# DRLPWM.net
KiCad netlist of a schematic drawn in Altium Designer
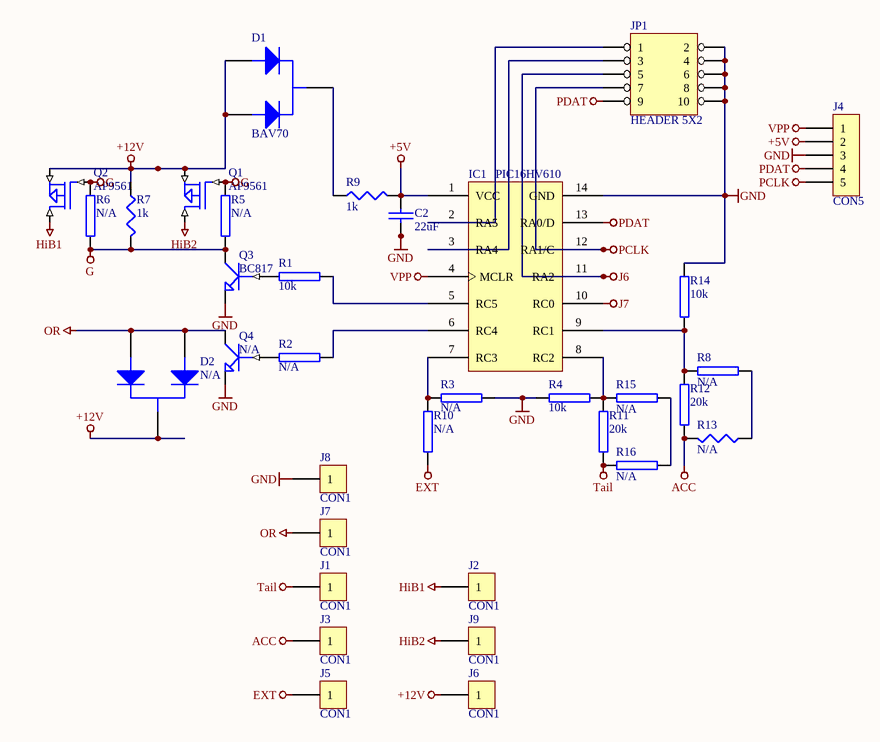
[diagram p0: DRLPWM.SchDoc]

(export (version "E")
  (design (tool "Eeschema 10.0.6"))
  (components
    (comp (ref "C2") (value "22uF") (footprint "0805") (libsource (lib "*") (part "CAP")))
    (comp (ref "D1")
      (value "BAV70")
      (footprint "SOT-23")
      (libsource (lib "Devices") (part "DUAL DIODE BAV70"))
    )
    (comp (ref "D2") (value "N/A") (footprint "SOT-23") (libsource (lib "Devices") (part "DUAL DIODE BAV70")))
    (comp (ref "IC1") (value "PIC16HV610") (footprint "SO-14") (libsource (lib "*") (part "PIC16HV610")))
    (comp (ref "J1")
      (value "CON1")
      (footprint "SIP1 - WIRE")
      (description "Connector")
      (libsource (lib "Miscellaneous Devices") (part "CON1"))
    )
    (comp (ref "J2")
      (value "CON1")
      (footprint "SIP1 - WIRE")
      (description "Connector")
      (libsource (lib "Miscellaneous Devices") (part "CON1"))
    )
    (comp (ref "J3")
      (value "CON1")
      (footprint "SIP1 - WIRE")
      (description "Connector")
      (libsource (lib "Miscellaneous Devices") (part "CON1"))
    )
    (comp (ref "J4")
      (value "CON5")
      (footprint "SIP5 - PGM")
      (description "Connector")
      (libsource (lib "Miscellaneous Devices") (part "CON5"))
    )
    (comp (ref "J5")
      (value "CON1")
      (footprint "SIP1 - WIRE")
      (description "Connector")
      (libsource (lib "Miscellaneous Devices") (part "CON1"))
    )
    (comp (ref "J6")
      (value "CON1")
      (footprint "SIP1 - WIRE")
      (description "Connector")
      (libsource (lib "Miscellaneous Devices") (part "CON1"))
    )
    (comp (ref "J7")
      (value "CON1")
      (footprint "SIP1 - WIRE")
      (description "Connector")
      (libsource (lib "Miscellaneous Devices") (part "CON1"))
    )
    (comp (ref "J8")
      (value "CON1")
      (footprint "SIP1 - WIRE")
      (description "Connector")
      (libsource (lib "Miscellaneous Devices") (part "CON1"))
    )
    (comp (ref "J9")
      (value "CON1")
      (footprint "SIP1 - WIRE")
      (description "Connector")
      (libsource (lib "Miscellaneous Devices") (part "CON1"))
    )
    (comp (ref "JP1")
      (value "HEADER 5X2")
      (footprint "IDC10")
      (libsource (lib "Miscellaneous Devices") (part "HEADER 5X2"))
    )
    (comp (ref "Q1") (value "AP9561") (footprint "D-Pack") (libsource (lib "*") (part "MOSFET P")))
    (comp (ref "Q2") (value "AP9561") (footprint "D-Pack") (libsource (lib "*") (part "MOSFET P")))
    (comp (ref "Q3")
      (value "BC817")
      (footprint "SOT-23")
      (description "NPN Transistor")
      (libsource (lib "Miscellaneous Devices") (part "NPN1"))
    )
    (comp (ref "Q4")
      (value "N/A")
      (footprint "SOT-23")
      (description "NPN Transistor")
      (libsource (lib "Miscellaneous Devices") (part "NPN1"))
    )
    (comp (ref "R1") (value "10k") (footprint "0805") (libsource (lib "*") (part "RES2")))
    (comp (ref "R2") (value "N/A") (footprint "0805") (libsource (lib "*") (part "RES2")))
    (comp (ref "R3") (value "N/A") (footprint "0805") (libsource (lib "*") (part "RES2")))
    (comp (ref "R4") (value "10k") (footprint "0805") (libsource (lib "*") (part "RES2")))
    (comp (ref "R5") (value "N/A") (footprint "0805") (libsource (lib "*") (part "RES2")))
    (comp (ref "R6") (value "N/A") (footprint "0805") (libsource (lib "*") (part "RES2")))
    (comp (ref "R7") (value "1k") (footprint "1206") (libsource (lib "Miscellaneous Devices") (part "RES1")))
    (comp (ref "R8") (value "N/A") (footprint "0805") (libsource (lib "*") (part "RES2")))
    (comp (ref "R9") (value "1k") (footprint "1206") (libsource (lib "Miscellaneous Devices") (part "RES1")))
    (comp (ref "R10") (value "N/A") (footprint "0805") (libsource (lib "*") (part "RES2")))
    (comp (ref "R11") (value "20k") (footprint "0805") (libsource (lib "*") (part "RES2")))
    (comp (ref "R12") (value "20k") (footprint "0805") (libsource (lib "*") (part "RES2")))
    (comp (ref "R13")
      (value "N/A")
      (footprint "0805")
      (libsource (lib "Miscellaneous Devices") (part "RES1"))
    )
    (comp (ref "R14") (value "10k") (footprint "0805") (libsource (lib "*") (part "RES2")))
    (comp (ref "R15") (value "N/A") (footprint "0805") (libsource (lib "*") (part "RES2")))
    (comp (ref "R16") (value "N/A") (footprint "0805") (libsource (lib "*") (part "RES2")))
  )
  (nets
    (net (code "1") (name "+5V") (class "Default")
      (node (ref "C2") (pin "1") (pintype "passive"))
      (node (ref "IC1") (pin "1") (pinfunction "VCC_1") (pintype "power_in"))
      (node (ref "J4") (pin "2") (pinfunction "2_2") (pintype "passive"))
      (node (ref "R9") (pin "2") (pinfunction "2_2") (pintype "passive"))
    )
    (net (code "2") (name "+12V") (class "Default")
      (node (ref "D1") (pin "1") (pinfunction "A1_1") (pintype "passive"))
      (node (ref "D1") (pin "3") (pinfunction "A2_3") (pintype "passive"))
      (node (ref "D2") (pin "2") (pinfunction "K_2") (pintype "passive"))
      (node (ref "J6") (pin "1") (pinfunction "1_1") (pintype "passive"))
      (node (ref "Q1") (pin "3") (pinfunction "SOURCE_3") (pintype "input"))
      (node (ref "Q2") (pin "3") (pinfunction "SOURCE_3") (pintype "input"))
      (node (ref "R7") (pin "1") (pinfunction "1_1") (pintype "passive"))
    )
    (net (code "3") (name "ACC") (class "Default")
      (node (ref "J3") (pin "1") (pinfunction "1_1") (pintype "passive"))
      (node (ref "R12") (pin "1") (pintype "passive"))
      (node (ref "R13") (pin "2") (pinfunction "2_2") (pintype "passive"))
    )
    (net (code "4") (name "EXT") (class "Default")
      (node (ref "J5") (pin "1") (pinfunction "1_1") (pintype "passive"))
      (node (ref "R10") (pin "1") (pintype "passive"))
    )
    (net (code "5") (name "G") (class "Default")
      (node (ref "Q1") (pin "1") (pinfunction "GATE_1") (pintype "input"))
      (node (ref "Q2") (pin "1") (pinfunction "GATE_1") (pintype "input"))
      (node (ref "Q3") (pin "2") (pinfunction "C_2") (pintype "passive"))
      (node (ref "R5") (pin "1") (pintype "passive"))
      (node (ref "R5") (pin "2") (pintype "passive"))
      (node (ref "R6") (pin "1") (pintype "passive"))
      (node (ref "R6") (pin "2") (pintype "passive"))
      (node (ref "R7") (pin "2") (pinfunction "2_2") (pintype "passive"))
    )
    (net (code "6") (name "GND") (class "Default")
      (node (ref "C2") (pin "2") (pintype "passive"))
      (node (ref "IC1") (pin "14") (pinfunction "GND_14") (pintype "power_in"))
      (node (ref "J4") (pin "3") (pinfunction "3_3") (pintype "passive"))
      (node (ref "J8") (pin "1") (pinfunction "1_1") (pintype "passive"))
      (node (ref "JP1") (pin "10") (pinfunction "10_10") (pintype "passive"))
      (node (ref "JP1") (pin "2") (pinfunction "2_2") (pintype "passive"))
      (node (ref "JP1") (pin "4") (pinfunction "4_4") (pintype "passive"))
      (node (ref "JP1") (pin "6") (pinfunction "6_6") (pintype "passive"))
      (node (ref "JP1") (pin "8") (pinfunction "8_8") (pintype "passive"))
      (node (ref "Q3") (pin "3") (pinfunction "E_3") (pintype "passive"))
      (node (ref "Q4") (pin "3") (pinfunction "E_3") (pintype "passive"))
      (node (ref "R14") (pin "2") (pintype "passive"))
      (node (ref "R3") (pin "2") (pintype "passive"))
      (node (ref "R4") (pin "1") (pintype "passive"))
    )
    (net (code "7") (name "HiB1") (class "Default")
      (node (ref "J2") (pin "1") (pinfunction "1_1") (pintype "passive"))
      (node (ref "Q2") (pin "2") (pinfunction "DRAIN_2") (pintype "input"))
    )
    (net (code "8") (name "HiB2") (class "Default")
      (node (ref "J9") (pin "1") (pinfunction "1_1") (pintype "passive"))
      (node (ref "Q1") (pin "2") (pinfunction "DRAIN_2") (pintype "input"))
    )
    (net (code "9") (name "J6") (class "Default")
      (node (ref "IC1") (pin "11") (pinfunction "RA2_11") (pintype "passive"))
      (node (ref "JP1") (pin "5") (pinfunction "5_5") (pintype "passive"))
    )
    (net (code "10") (name "J7") (class "Default")
      (node (ref "IC1") (pin "10") (pinfunction "RC0_10") (pintype "passive"))
    )
    (net (code "11") (name "Net-(D1-K)") (class "Default")
      (node (ref "D1") (pin "2") (pinfunction "K_2") (pintype "passive"))
      (node (ref "R9") (pin "1") (pinfunction "1_1") (pintype "passive"))
    )
    (net (code "12") (name "Net-(IC1-RA4)") (class "Default")
      (node (ref "IC1") (pin "3") (pinfunction "RA4_3") (pintype "passive"))
      (node (ref "JP1") (pin "3") (pinfunction "3_3") (pintype "passive"))
    )
    (net (code "13") (name "Net-(IC1-RA5)") (class "Default")
      (node (ref "IC1") (pin "2") (pinfunction "RA5_2") (pintype "passive"))
      (node (ref "JP1") (pin "1") (pinfunction "1_1") (pintype "passive"))
    )
    (net (code "14") (name "Net-(IC1-RC1)") (class "Default")
      (node (ref "IC1") (pin "9") (pinfunction "RC1_9") (pintype "passive"))
      (node (ref "R12") (pin "2") (pintype "passive"))
      (node (ref "R14") (pin "1") (pintype "passive"))
      (node (ref "R8") (pin "1") (pintype "passive"))
    )
    (net (code "15") (name "Net-(IC1-RC2)") (class "Default")
      (node (ref "IC1") (pin "8") (pinfunction "RC2_8") (pintype "passive"))
      (node (ref "R11") (pin "2") (pintype "passive"))
      (node (ref "R15") (pin "1") (pintype "passive"))
      (node (ref "R4") (pin "2") (pintype "passive"))
    )
    (net (code "16") (name "Net-(IC1-RC3)") (class "Default")
      (node (ref "IC1") (pin "7") (pinfunction "RC3_7") (pintype "passive"))
      (node (ref "R10") (pin "2") (pintype "passive"))
      (node (ref "R3") (pin "1") (pintype "passive"))
    )
    (net (code "17") (name "Net-(IC1-RC4)") (class "Default")
      (node (ref "IC1") (pin "6") (pinfunction "RC4_6") (pintype "passive"))
      (node (ref "R2") (pin "2") (pintype "passive"))
    )
    (net (code "18") (name "Net-(IC1-RC5)") (class "Default")
      (node (ref "IC1") (pin "5") (pinfunction "RC5_5") (pintype "passive"))
      (node (ref "R1") (pin "2") (pintype "passive"))
    )
    (net (code "19") (name "Net-(Q3-B)") (class "Default")
      (node (ref "Q3") (pin "1") (pinfunction "B_1") (pintype "input"))
      (node (ref "R1") (pin "1") (pintype "passive"))
    )
    (net (code "20") (name "Net-(Q4-B)") (class "Default")
      (node (ref "Q4") (pin "1") (pinfunction "B_1") (pintype "input"))
      (node (ref "R2") (pin "1") (pintype "passive"))
    )
    (net (code "21") (name "Net-(R13-Pad1)") (class "Default")
      (node (ref "R13") (pin "1") (pinfunction "1_1") (pintype "passive"))
      (node (ref "R8") (pin "2") (pintype "passive"))
    )
    (net (code "22") (name "Net-(R15-Pad2)") (class "Default")
      (node (ref "R15") (pin "2") (pintype "passive"))
      (node (ref "R16") (pin "2") (pintype "passive"))
    )
    (net (code "23") (name "OR") (class "Default")
      (node (ref "D2") (pin "1") (pinfunction "A1_1") (pintype "passive"))
      (node (ref "D2") (pin "3") (pinfunction "A2_3") (pintype "passive"))
      (node (ref "J7") (pin "1") (pinfunction "1_1") (pintype "passive"))
      (node (ref "Q4") (pin "2") (pinfunction "C_2") (pintype "passive"))
    )
    (net (code "24") (name "PCLK") (class "Default")
      (node (ref "IC1") (pin "12") (pinfunction "RA1/C_12") (pintype "passive"))
      (node (ref "J4") (pin "5") (pinfunction "5_5") (pintype "passive"))
      (node (ref "JP1") (pin "7") (pinfunction "7_7") (pintype "passive"))
    )
    (net (code "25") (name "PDAT") (class "Default")
      (node (ref "IC1") (pin "13") (pinfunction "RA0/D_13") (pintype "passive"))
      (node (ref "J4") (pin "4") (pinfunction "4_4") (pintype "passive"))
      (node (ref "JP1") (pin "9") (pinfunction "9_9") (pintype "passive"))
    )
    (net (code "26") (name "Tail") (class "Default")
      (node (ref "J1") (pin "1") (pinfunction "1_1") (pintype "passive"))
      (node (ref "R11") (pin "1") (pintype "passive"))
      (node (ref "R16") (pin "1") (pintype "passive"))
    )
    (net (code "27") (name "VPP") (class "Default")
      (node (ref "IC1") (pin "4") (pinfunction "MCLR_4") (pintype "passive"))
      (node (ref "J4") (pin "1") (pinfunction "1_1") (pintype "passive"))
    )
  )
)
